# Sheet7.net
KiCad netlist of a schematic drawn in Altium Designer
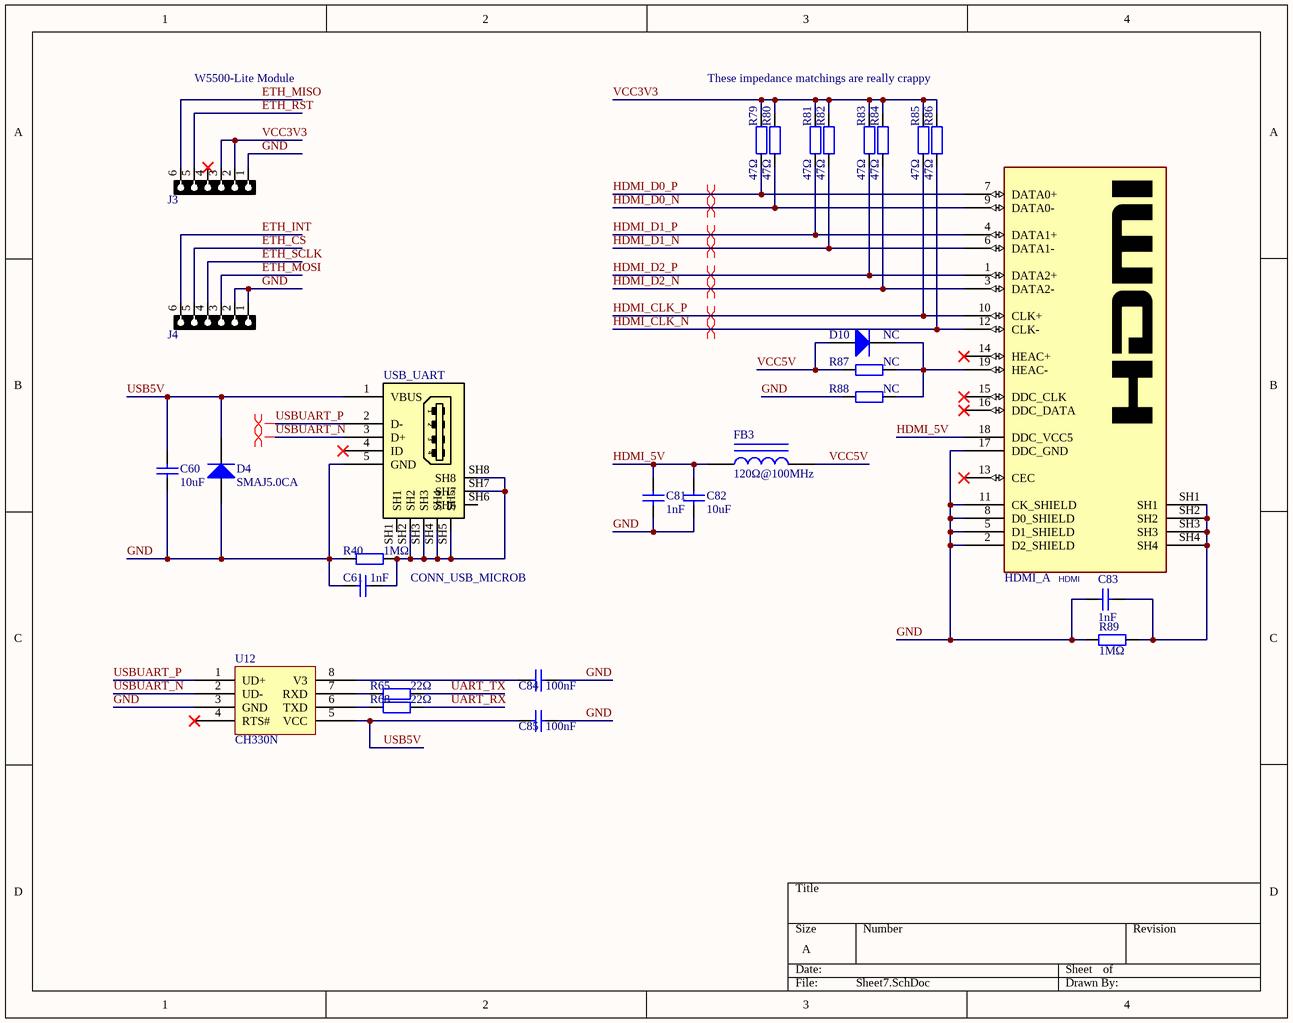
[diagram p0: Sheet7.SchDoc]

(export (version "E")
  (design (tool "Eeschema 10.0.6"))
  (components
    (comp (ref "C60")
      (value "10uF")
      (footprint "1206_C")
      (description "贴片电容")
      (libsource (lib "Cap") (part "1206 10uF (106) 10% 50V"))
    )
    (comp (ref "C61")
      (value "1nF")
      (footprint "0805_C")
      (description "贴片电容")
      (libsource (lib "Cap") (part "0805 1nF (102) 10% 50V"))
    )
    (comp (ref "C81")
      (value "1nF")
      (footprint "0805_C")
      (description "贴片电容")
      (libsource (lib "Cap") (part "0805 1nF (102) 10% 50V"))
    )
    (comp (ref "C82")
      (value "10uF")
      (footprint "0603_C")
      (description "贴片电容")
      (libsource (lib "Cap") (part "0603 10uF (106) 10% 10V"))
    )
    (comp (ref "C83")
      (value "1nF")
      (footprint "0805_C")
      (description "贴片电容")
      (libsource (lib "Cap") (part "0805 1nF (102) 10% 50V"))
    )
    (comp (ref "C84")
      (value "100nF")
      (footprint "1206_C")
      (description "贴片电容")
      (libsource (lib "Cap") (part "1206 100nF (104) 10% 50V"))
    )
    (comp (ref "C85")
      (value "100nF")
      (footprint "1206_C")
      (description "贴片电容")
      (libsource (lib "Cap") (part "1206 100nF (104) 10% 50V"))
    )
    (comp (ref "D4")
      (value "SMAJ5.0CA")
      (footprint "SMA(DO-214AC)_S1")
      (description "二极管 TVS")
      (libsource (lib "Diode") (part "SMA(DO-214AC) SS210"))
    )
    (comp (ref "D10")
      (value "NC")
      (footprint "SMA(DO-214AC)_S1")
      (description "二极管 TVS")
      (libsource (lib "Diode") (part "SMA(DO-214AC) SS210"))
    )
    (comp (ref "FB3")
      (value "120Ω@100MHz")
      (footprint "0805_L")
      (description "贴片磁珠")
      (libsource (lib "IUD") (part "0805 600Ω 25% 100MHz"))
    )
    (comp (ref "HDMI")
      (value "HDMI_A")
      (footprint "HDMI_A")
      (description "CONN, HDMI, Receptacle, TYPE A, 19P, RIGH-ANGLE")
      (fields
        (field (name "MANF") "Molex, WURTH")
        (field (name "MANF_P#") "47151-0001, 500254-1927, 685119134923")
      )
      (libsource (lib "Connector Display") (part "CONN_HDMI_A"))
    )
    (comp (ref "J3")
      (value "HDRF6")
      (footprint "HDR_F_1X6")
      (description "CONN, HEADER, Female, pitch: 2.54mm, 6POS")
      (libsource (lib "Connector Header 254") (part "HDR_F_1X6"))
    )
    (comp (ref "J4")
      (value "HDRF6")
      (footprint "HDR_F_1X6")
      (description "CONN, HEADER, Female, pitch: 2.54mm, 6POS")
      (libsource (lib "Connector Header 254") (part "HDR_F_1X6"))
    )
    (comp (ref "R40")
      (value "1MΩ")
      (footprint "0805_R")
      (description "贴片电阻")
      (libsource (lib "RES") (part "0805 1MΩ (1004) 1%"))
    )
    (comp (ref "R65")
      (value "22Ω")
      (footprint "1206_R")
      (description "贴片电阻")
      (libsource (lib "RES") (part "1206 22Ω (22R0) 1%"))
    )
    (comp (ref "R68")
      (value "22Ω")
      (footprint "1206_R")
      (description "贴片电阻")
      (libsource (lib "RES") (part "1206 22Ω (22R0) 1%"))
    )
    (comp (ref "R79")
      (value "47Ω")
      (footprint "0805_R")
      (description "贴片电阻")
      (libsource (lib "RES") (part "0805 47Ω (47R0) 1%"))
    )
    (comp (ref "R80")
      (value "47Ω")
      (footprint "0805_R")
      (description "贴片电阻")
      (libsource (lib "RES") (part "0805 47Ω (47R0) 1%"))
    )
    (comp (ref "R81")
      (value "47Ω")
      (footprint "0805_R")
      (description "贴片电阻")
      (libsource (lib "RES") (part "0805 47Ω (47R0) 1%"))
    )
    (comp (ref "R82")
      (value "47Ω")
      (footprint "0805_R")
      (description "贴片电阻")
      (libsource (lib "RES") (part "0805 47Ω (47R0) 1%"))
    )
    (comp (ref "R83")
      (value "47Ω")
      (footprint "0805_R")
      (description "贴片电阻")
      (libsource (lib "RES") (part "0805 47Ω (47R0) 1%"))
    )
    (comp (ref "R84")
      (value "47Ω")
      (footprint "0805_R")
      (description "贴片电阻")
      (libsource (lib "RES") (part "0805 47Ω (47R0) 1%"))
    )
    (comp (ref "R85")
      (value "47Ω")
      (footprint "0805_R")
      (description "贴片电阻")
      (libsource (lib "RES") (part "0805 47Ω (47R0) 1%"))
    )
    (comp (ref "R86")
      (value "47Ω")
      (footprint "0805_R")
      (description "贴片电阻")
      (libsource (lib "RES") (part "0805 47Ω (47R0) 1%"))
    )
    (comp (ref "R87")
      (value "NC")
      (footprint "0805_R")
      (description "贴片电阻")
      (libsource (lib "") (part "0805 1MΩ (1004) 1%_1"))
    )
    (comp (ref "R88")
      (value "NC")
      (footprint "0805_R")
      (description "贴片电阻")
      (libsource (lib "") (part "0805 1MΩ (1004) 1%_1"))
    )
    (comp (ref "R89")
      (value "1MΩ")
      (footprint "0805_R")
      (description "贴片电阻")
      (libsource (lib "") (part "0805 1MΩ (1004) 1%_1"))
    )
    (comp (ref "U12")
      (value "CH330N")
      (footprint "SOIC-8_150mil")
      (description "PSRAM, 150mil SOP-8")
      (libsource (lib "IC") (part "EEPROM/AT24C256C-SSHL-T_[C6482]"))
    )
    (comp (ref "USB_UART")
      (value "CONN_USB_MICROB")
      (footprint "USB_MICRO_B_BM_SHT1")
      (description "CONN, USB, MICRO B, R/A, SMD, BOTTOM MOUNT, SHT")
      (fields (field (name "MANF_P#") "47590-0001") (field (name "MANF") "MOLEX"))
      (libsource (lib "Connector USB") (part "CONN_USB_MICRO_B_BM_SHT1"))
    )
  )
  (nets
    (net (code "1") (name "/ETH_CS") (class "Default")
      (node (ref "J4") (pin "5") (pinfunction "5_5") (pintype "passive"))
    )
    (net (code "2") (name "/ETH_INT") (class "Default")
      (node (ref "J4") (pin "6") (pinfunction "6_6") (pintype "passive"))
    )
    (net (code "3") (name "/ETH_MISO") (class "Default")
      (node (ref "J3") (pin "6") (pinfunction "6_6") (pintype "passive"))
    )
    (net (code "4") (name "/ETH_MOSI") (class "Default")
      (node (ref "J4") (pin "3") (pinfunction "3_3") (pintype "passive"))
    )
    (net (code "5") (name "/ETH_RST") (class "Default")
      (node (ref "J3") (pin "5") (pinfunction "5_5") (pintype "passive"))
    )
    (net (code "6") (name "/ETH_SCLK") (class "Default")
      (node (ref "J4") (pin "4") (pinfunction "4_4") (pintype "passive"))
    )
    (net (code "7") (name "/GND") (class "Default")
      (node (ref "C60") (pin "1") (pinfunction "1_1") (pintype "passive"))
      (node (ref "C61") (pin "1") (pinfunction "1_1") (pintype "passive"))
      (node (ref "C81") (pin "2") (pinfunction "2_2") (pintype "passive"))
      (node (ref "C82") (pin "1") (pinfunction "1_1") (pintype "passive"))
      (node (ref "C83") (pin "2") (pinfunction "2_2") (pintype "passive"))
      (node (ref "C84") (pin "2") (pinfunction "2_2") (pintype "passive"))
      (node (ref "C85") (pin "2") (pinfunction "2_2") (pintype "passive"))
      (node (ref "D4") (pin "1") (pinfunction "A_1") (pintype "passive"))
      (node (ref "HDMI") (pin "11") (pinfunction "CK_SHIELD_11") (pintype "passive"))
      (node (ref "HDMI") (pin "17") (pinfunction "DDC_GND_17") (pintype "passive"))
      (node (ref "HDMI") (pin "2") (pinfunction "D2_SHIELD_2") (pintype "passive"))
      (node (ref "HDMI") (pin "5") (pinfunction "D1_SHIELD_5") (pintype "passive"))
      (node (ref "HDMI") (pin "8") (pinfunction "D0_SHIELD_8") (pintype "passive"))
      (node (ref "J3") (pin "1") (pinfunction "1_1") (pintype "passive"))
      (node (ref "J4") (pin "1") (pinfunction "1_1") (pintype "passive"))
      (node (ref "J4") (pin "2") (pinfunction "2_2") (pintype "passive"))
      (node (ref "R40") (pin "1") (pinfunction "1_1") (pintype "passive"))
      (node (ref "R88") (pin "2") (pinfunction "2_2") (pintype "passive"))
      (node (ref "R89") (pin "2") (pinfunction "2_2") (pintype "passive"))
      (node (ref "U12") (pin "3") (pinfunction "GND_3") (pintype "passive"))
      (node (ref "USB_UART") (pin "5") (pinfunction "GND_5") (pintype "power_in"))
    )
    (net (code "8") (name "/HDMI_5V") (class "Default")
      (node (ref "C81") (pin "1") (pinfunction "1_1") (pintype "passive"))
      (node (ref "C82") (pin "2") (pinfunction "2_2") (pintype "passive"))
      (node (ref "FB3") (pin "1") (pinfunction "1_1") (pintype "passive"))
      (node (ref "HDMI") (pin "18") (pinfunction "DDC_VCC5_18") (pintype "passive"))
    )
    (net (code "9") (name "/HDMI_CLK_N") (class "Default")
      (node (ref "HDMI") (pin "12") (pinfunction "CLK-_12") (pintype "bidirectional"))
      (node (ref "R86") (pin "1") (pinfunction "1_1") (pintype "passive"))
    )
    (net (code "10") (name "/HDMI_CLK_P") (class "Default")
      (node (ref "HDMI") (pin "10") (pinfunction "CLK+_10") (pintype "bidirectional"))
      (node (ref "R85") (pin "1") (pinfunction "1_1") (pintype "passive"))
    )
    (net (code "11") (name "/HDMI_D0_N") (class "Default")
      (node (ref "HDMI") (pin "9") (pinfunction "DATA0-_9") (pintype "bidirectional"))
      (node (ref "R80") (pin "1") (pinfunction "1_1") (pintype "passive"))
    )
    (net (code "12") (name "/HDMI_D0_P") (class "Default")
      (node (ref "HDMI") (pin "7") (pinfunction "DATA0+_7") (pintype "bidirectional"))
      (node (ref "R79") (pin "1") (pinfunction "1_1") (pintype "passive"))
    )
    (net (code "13") (name "/HDMI_D1_N") (class "Default")
      (node (ref "HDMI") (pin "6") (pinfunction "DATA1-_6") (pintype "bidirectional"))
      (node (ref "R82") (pin "1") (pinfunction "1_1") (pintype "passive"))
    )
    (net (code "14") (name "/HDMI_D1_P") (class "Default")
      (node (ref "HDMI") (pin "4") (pinfunction "DATA1+_4") (pintype "bidirectional"))
      (node (ref "R81") (pin "1") (pinfunction "1_1") (pintype "passive"))
    )
    (net (code "15") (name "/HDMI_D2_N") (class "Default")
      (node (ref "HDMI") (pin "3") (pinfunction "DATA2-_3") (pintype "bidirectional"))
      (node (ref "R84") (pin "1") (pinfunction "1_1") (pintype "passive"))
    )
    (net (code "16") (name "/HDMI_D2_P") (class "Default")
      (node (ref "HDMI") (pin "1") (pinfunction "DATA2+_1") (pintype "bidirectional"))
      (node (ref "R83") (pin "1") (pinfunction "1_1") (pintype "passive"))
    )
    (net (code "17") (name "/UART_RX") (class "Default")
      (node (ref "R68") (pin "2") (pinfunction "2_2") (pintype "passive"))
    )
    (net (code "18") (name "/UART_TX") (class "Default")
      (node (ref "R65") (pin "2") (pinfunction "2_2") (pintype "passive"))
    )
    (net (code "19") (name "/USB5V") (class "Default")
      (node (ref "C60") (pin "2") (pinfunction "2_2") (pintype "passive"))
      (node (ref "C85") (pin "1") (pinfunction "1_1") (pintype "passive"))
      (node (ref "D4") (pin "2") (pinfunction "K_2") (pintype "passive"))
      (node (ref "U12") (pin "5") (pinfunction "VCC_5") (pintype "passive"))
      (node (ref "USB_UART") (pin "1") (pinfunction "VBUS_1") (pintype "power_in"))
    )
    (net (code "20") (name "/USBUART_N") (class "Default")
      (node (ref "U12") (pin "2") (pinfunction "UD-_2") (pintype "passive"))
      (node (ref "USB_UART") (pin "3") (pinfunction "D+_3") (pintype "passive"))
    )
    (net (code "21") (name "/USBUART_P") (class "Default")
      (node (ref "U12") (pin "1") (pinfunction "UD+_1") (pintype "passive"))
      (node (ref "USB_UART") (pin "2") (pinfunction "D-_2") (pintype "passive"))
    )
    (net (code "22") (name "/VCC3V3") (class "Default")
      (node (ref "J3") (pin "2") (pinfunction "2_2") (pintype "passive"))
      (node (ref "J3") (pin "3") (pinfunction "3_3") (pintype "passive"))
      (node (ref "R79") (pin "2") (pinfunction "2_2") (pintype "passive"))
      (node (ref "R80") (pin "2") (pinfunction "2_2") (pintype "passive"))
      (node (ref "R81") (pin "2") (pinfunction "2_2") (pintype "passive"))
      (node (ref "R82") (pin "2") (pinfunction "2_2") (pintype "passive"))
      (node (ref "R83") (pin "2") (pinfunction "2_2") (pintype "passive"))
      (node (ref "R84") (pin "2") (pinfunction "2_2") (pintype "passive"))
      (node (ref "R85") (pin "2") (pinfunction "2_2") (pintype "passive"))
      (node (ref "R86") (pin "2") (pinfunction "2_2") (pintype "passive"))
    )
    (net (code "23") (name "/VCC5V") (class "Default")
      (node (ref "D10") (pin "1") (pinfunction "A_1") (pintype "passive"))
      (node (ref "FB3") (pin "2") (pinfunction "2_2") (pintype "passive"))
      (node (ref "R87") (pin "2") (pinfunction "2_2") (pintype "passive"))
    )
    (net (code "24") (name "Net-(C61-Pad2)") (class "Default")
      (node (ref "C61") (pin "2") (pinfunction "2_2") (pintype "passive"))
      (node (ref "R40") (pin "2") (pinfunction "2_2") (pintype "passive"))
      (node (ref "USB_UART") (pin "SH2") (pinfunction "SH2_SH2") (pintype "passive"))
      (node (ref "USB_UART") (pin "SH3") (pinfunction "SH3_SH3") (pintype "passive"))
      (node (ref "USB_UART") (pin "SH4") (pinfunction "SH4_SH4") (pintype "passive"))
      (node (ref "USB_UART") (pin "SH5") (pinfunction "SH5_SH5") (pintype "passive"))
      (node (ref "USB_UART") (pin "SH7") (pinfunction "SH7_SH7") (pintype "passive"))
      (node (ref "USB_UART") (pin "SH8") (pinfunction "SH8_SH8") (pintype "passive"))
    )
    (net (code "25") (name "Net-(C83-Pad1)") (class "Default")
      (node (ref "C83") (pin "1") (pinfunction "1_1") (pintype "passive"))
      (node (ref "HDMI") (pin "SH1") (pinfunction "SH1_SH1") (pintype "passive"))
      (node (ref "HDMI") (pin "SH2") (pinfunction "SH2_SH2") (pintype "passive"))
      (node (ref "HDMI") (pin "SH3") (pinfunction "SH3_SH3") (pintype "passive"))
      (node (ref "HDMI") (pin "SH4") (pinfunction "SH4_SH4") (pintype "passive"))
      (node (ref "R89") (pin "1") (pinfunction "1_1") (pintype "passive"))
    )
    (net (code "26") (name "Net-(D10-K)") (class "Default")
      (node (ref "D10") (pin "2") (pinfunction "K_2") (pintype "passive"))
      (node (ref "HDMI") (pin "19") (pinfunction "HEAC-_19") (pintype "bidirectional"))
      (node (ref "R87") (pin "1") (pinfunction "1_1") (pintype "passive"))
      (node (ref "R88") (pin "1") (pinfunction "1_1") (pintype "passive"))
    )
    (net (code "27") (name "Net-(U12-RXD)") (class "Default")
      (node (ref "R65") (pin "1") (pinfunction "1_1") (pintype "passive"))
      (node (ref "U12") (pin "7") (pinfunction "RXD_7") (pintype "passive"))
    )
    (net (code "28") (name "Net-(U12-TXD)") (class "Default")
      (node (ref "R68") (pin "1") (pinfunction "1_1") (pintype "passive"))
      (node (ref "U12") (pin "6") (pinfunction "TXD_6") (pintype "passive"))
    )
    (net (code "29") (name "Net-(U12-V3)") (class "Default")
      (node (ref "C84") (pin "1") (pinfunction "1_1") (pintype "passive"))
      (node (ref "U12") (pin "8") (pinfunction "V3_8") (pintype "passive"))
    )
    (net (code "30") (name "unconnected-(HDMI-CEC-Pad13)") (class "Default")
      (node (ref "HDMI") (pin "13") (pinfunction "CEC_13") (pintype "bidirectional+no_connect"))
    )
    (net (code "31") (name "unconnected-(HDMI-DDC_CLK-Pad15)") (class "Default")
      (node (ref "HDMI") (pin "15") (pinfunction "DDC_CLK_15") (pintype "bidirectional+no_connect"))
    )
    (net (code "32") (name "unconnected-(HDMI-DDC_DATA-Pad16)") (class "Default")
      (node (ref "HDMI") (pin "16") (pinfunction "DDC_DATA_16") (pintype "bidirectional+no_connect"))
    )
    (net (code "33") (name "unconnected-(HDMI-HEAC+-Pad14)") (class "Default")
      (node (ref "HDMI") (pin "14") (pinfunction "HEAC+_14") (pintype "bidirectional+no_connect"))
    )
    (net (code "34") (name "unconnected-(J3-Pad4)") (class "Default")
      (node (ref "J3") (pin "4") (pinfunction "4_4") (pintype "passive+no_connect"))
    )
    (net (code "35") (name "unconnected-(U12-RTS#-Pad4)") (class "Default")
      (node (ref "U12") (pin "4") (pinfunction "RTS#_4") (pintype "passive+no_connect"))
    )
    (net (code "36") (name "unconnected-(USB_UART-ID-Pad4)") (class "Default")
      (node (ref "USB_UART") (pin "4") (pinfunction "ID_4") (pintype "power_in+no_connect"))
    )
    (net (code "37") (name "unconnected-(USB_UART-PadSH1)") (class "Default")
      (node (ref "USB_UART") (pin "SH1") (pinfunction "SH1_SH1") (pintype "passive"))
    )
    (net (code "38") (name "unconnected-(USB_UART-PadSH6)") (class "Default")
      (node (ref "USB_UART") (pin "SH6") (pinfunction "SH6_SH6") (pintype "passive"))
    )
  )
)
